# V1-MOUSE-REVIEW.net
KiCad netlist of a schematic drawn in EAGLE
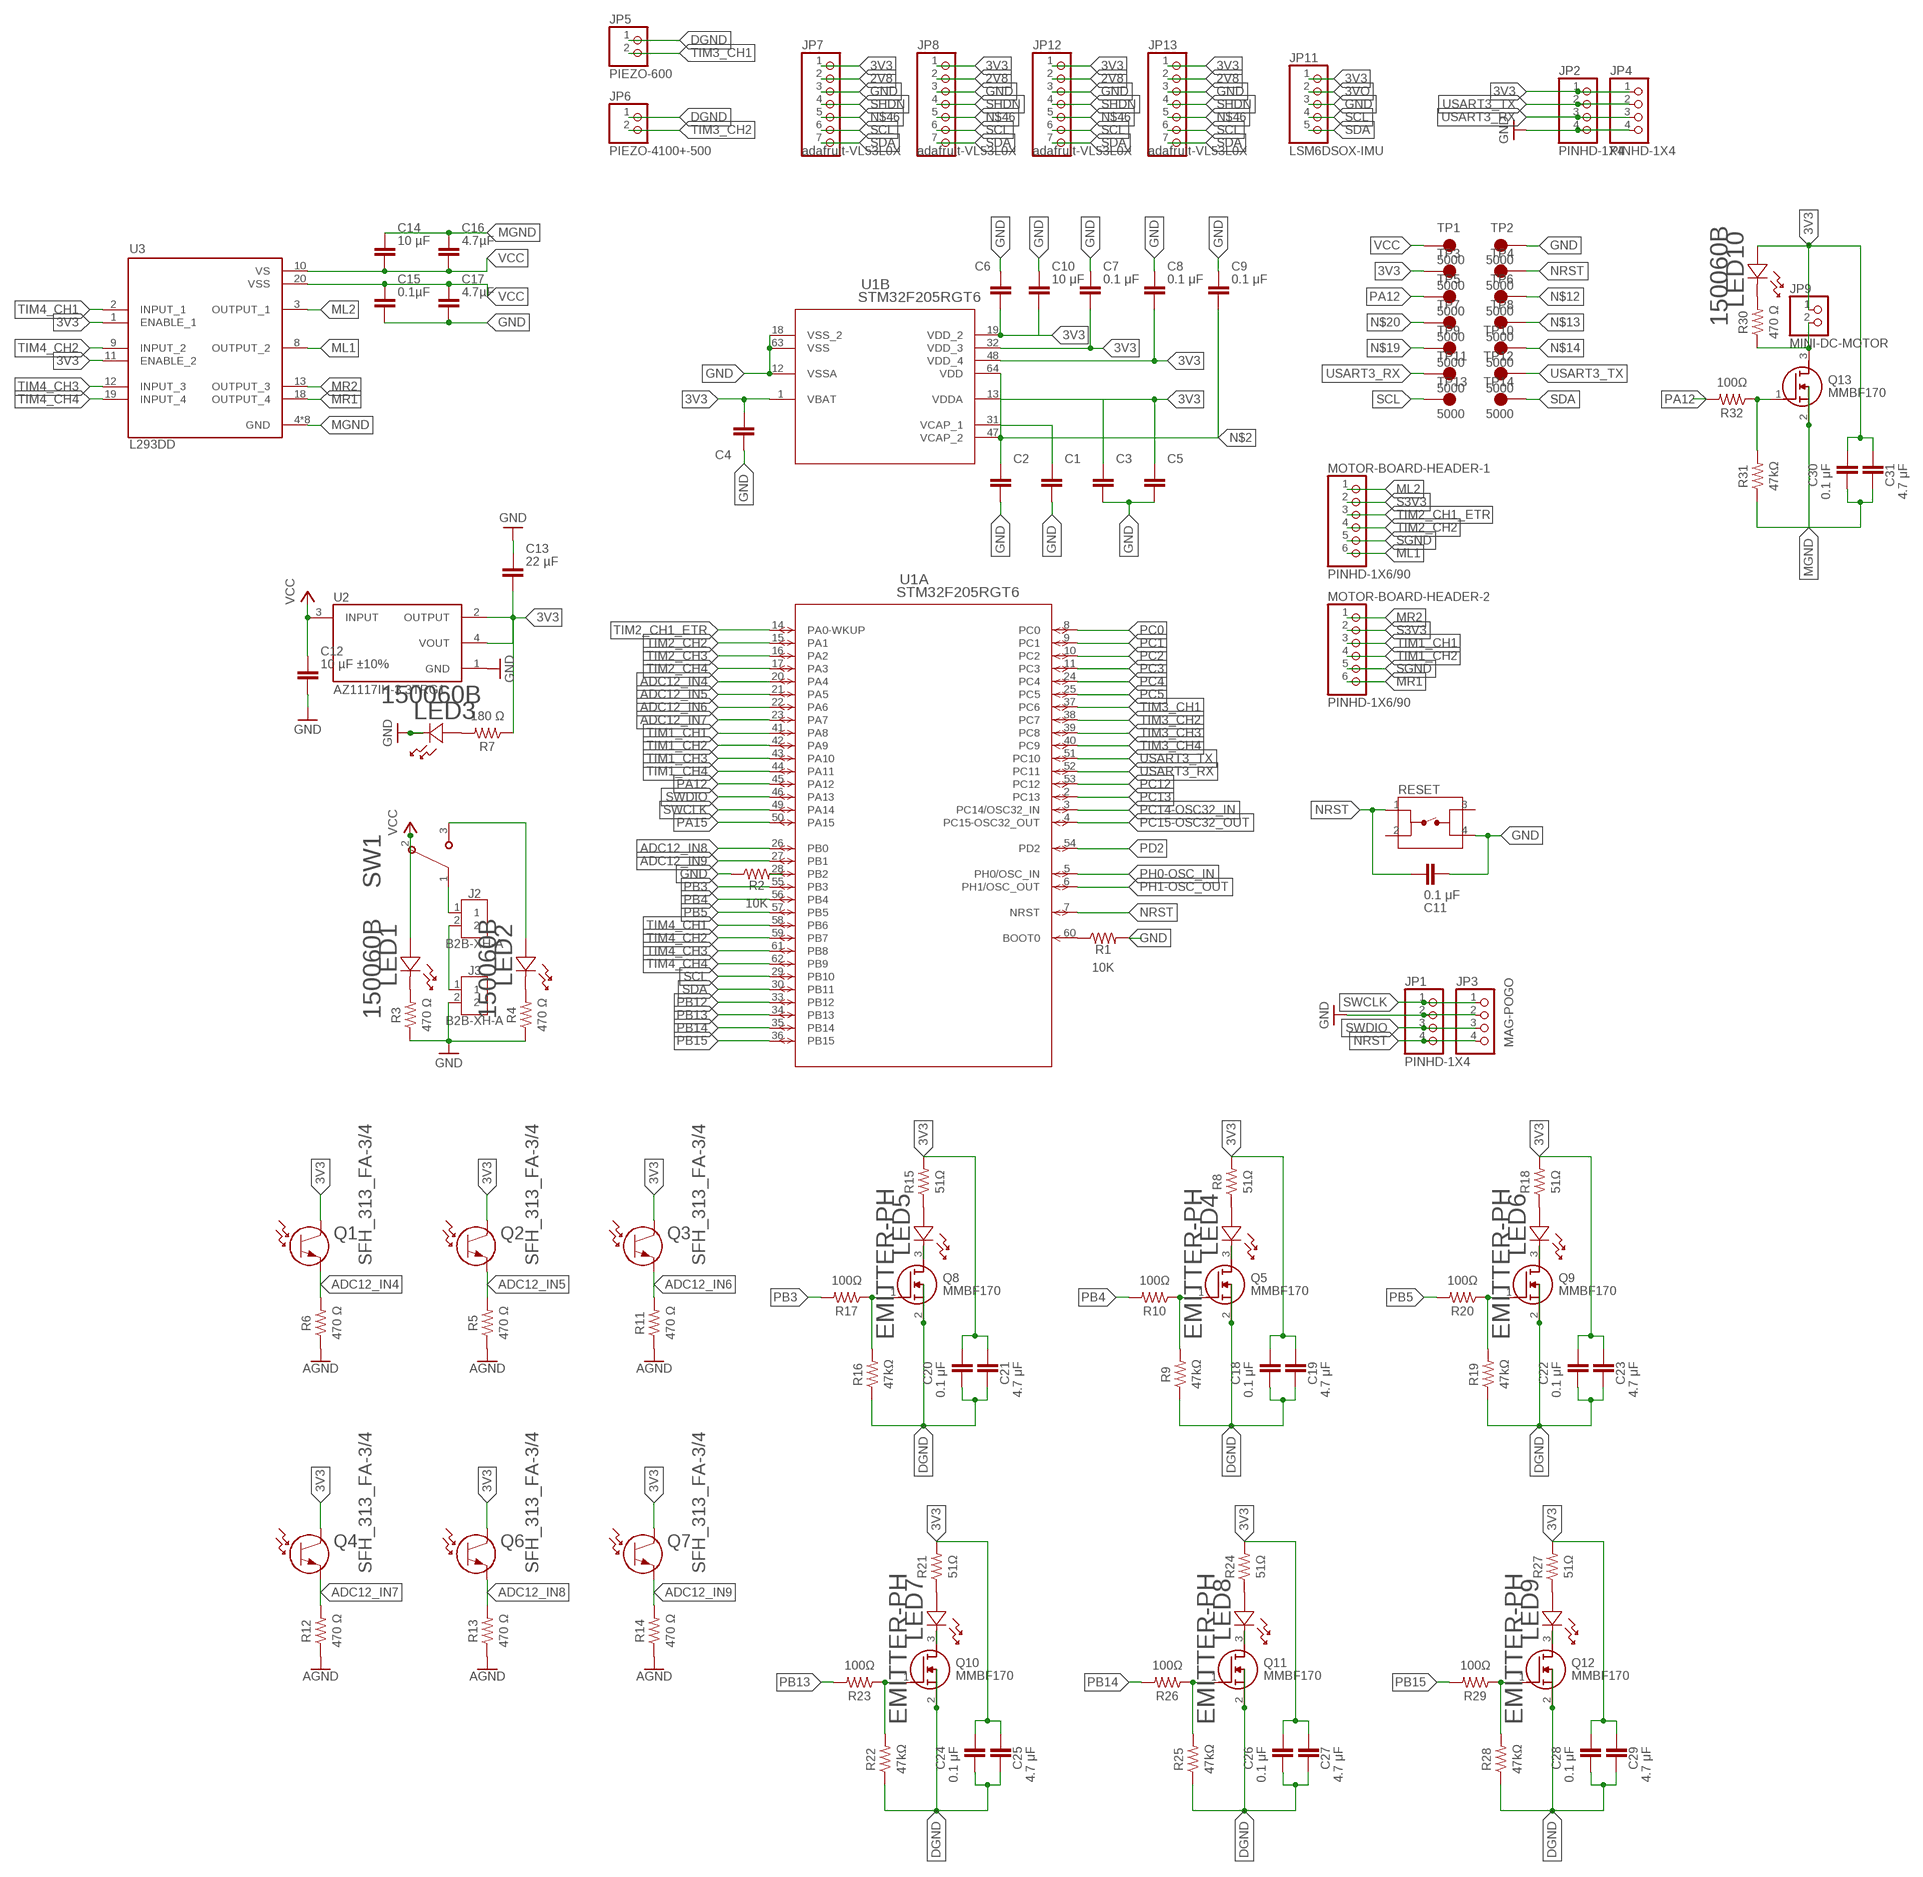
[diagram p0: schematic, sheet 1]

(export (version "E")
  (design (tool "Eeschema 10.0.6"))
  (components
    (comp (ref "C1")
      (value "2.2 μF")
      (footprint "eagle-import:CAPC1608X85")
      (libsource (lib "eagle-import") (part "CCHIP-0603(1608-METRIC)_"))
    )
    (comp (ref "C2")
      (value "2.2 μF")
      (footprint "eagle-import:CAPC1608X85")
      (libsource (lib "eagle-import") (part "CCHIP-0603(1608-METRIC)_"))
    )
    (comp (ref "C3")
      (value "0.1 μF")
      (footprint "eagle-import:CAPC1608X85")
      (libsource (lib "eagle-import") (part "CCHIP-0603(1608-METRIC)_"))
    )
    (comp (ref "C4")
      (value "0.1 μF")
      (footprint "eagle-import:CAPC1608X85")
      (libsource (lib "eagle-import") (part "CCHIP-0603(1608-METRIC)_"))
    )
    (comp (ref "C5")
      (value "1 μF")
      (footprint "eagle-import:CAPC1608X85")
      (libsource (lib "eagle-import") (part "CCHIP-0603(1608-METRIC)_"))
    )
    (comp (ref "C6")
      (value "0.1 μF")
      (footprint "eagle-import:CAPC1608X85")
      (libsource (lib "eagle-import") (part "CCHIP-0603(1608-METRIC)_"))
    )
    (comp (ref "C7")
      (value "0.1 μF")
      (footprint "eagle-import:CAPC1608X85")
      (libsource (lib "eagle-import") (part "Capacitor2_CCHIP-0603(1608-METRIC)_"))
    )
    (comp (ref "C8")
      (value "0.1 μF")
      (footprint "eagle-import:CAPC1608X85")
      (libsource (lib "eagle-import") (part "Capacitor2_CCHIP-0603(1608-METRIC)_"))
    )
    (comp (ref "C9")
      (value "0.1 μF")
      (footprint "eagle-import:CAPC1608X85")
      (libsource (lib "eagle-import") (part "Capacitor2_CCHIP-0603(1608-METRIC)_"))
    )
    (comp (ref "C10")
      (value "10 μF")
      (footprint "eagle-import:CAPC1608X85")
      (libsource (lib "eagle-import") (part "Capacitor2_CCHIP-0603(1608-METRIC)_"))
    )
    (comp (ref "C11")
      (value "0.1 μF")
      (footprint "eagle-import:CAPC1608X85")
      (libsource (lib "eagle-import") (part "Capacitor2_CCHIP-0603(1608-METRIC)_"))
    )
    (comp (ref "C12")
      (value "10 µF ±10%")
      (footprint "eagle-import:CAPC1608X85")
      (libsource (lib "eagle-import") (part "CCHIP-0603(1608-METRIC)_"))
    )
    (comp (ref "C13")
      (value "22 µF")
      (footprint "eagle-import:CAPC1608X85")
      (libsource (lib "eagle-import") (part "CCHIP-0603(1608-METRIC)_"))
    )
    (comp (ref "C14")
      (value "10 µF")
      (footprint "eagle-import:CAPC1608X85")
      (libsource (lib "eagle-import") (part "CCHIP-0603(1608-METRIC)_"))
    )
    (comp (ref "C15")
      (value "0.1µF")
      (footprint "eagle-import:CAPC1608X85")
      (libsource (lib "eagle-import") (part "CCHIP-0603(1608-METRIC)_"))
    )
    (comp (ref "C16")
      (value "4.7µF")
      (footprint "eagle-import:CAPC1608X85")
      (libsource (lib "eagle-import") (part "CCHIP-0603(1608-METRIC)_"))
    )
    (comp (ref "C17")
      (value "4.7µF")
      (footprint "eagle-import:CAPC1608X85")
      (libsource (lib "eagle-import") (part "CCHIP-0603(1608-METRIC)_"))
    )
    (comp (ref "C18")
      (value "0.1 μF")
      (footprint "eagle-import:CAPC1608X85")
      (libsource (lib "eagle-import") (part "Capacitor2_CCHIP-0603(1608-METRIC)_"))
    )
    (comp (ref "C19")
      (value "4.7 μF")
      (footprint "eagle-import:CAPC1608X85")
      (libsource (lib "eagle-import") (part "Capacitor2_CCHIP-0603(1608-METRIC)_"))
    )
    (comp (ref "C20")
      (value "0.1 μF")
      (footprint "eagle-import:CAPC1608X85")
      (libsource (lib "eagle-import") (part "Capacitor2_CCHIP-0603(1608-METRIC)_"))
    )
    (comp (ref "C21")
      (value "4.7 μF")
      (footprint "eagle-import:CAPC1608X85")
      (libsource (lib "eagle-import") (part "Capacitor2_CCHIP-0603(1608-METRIC)_"))
    )
    (comp (ref "C22")
      (value "0.1 μF")
      (footprint "eagle-import:CAPC1608X85")
      (libsource (lib "eagle-import") (part "Capacitor2_CCHIP-0603(1608-METRIC)_"))
    )
    (comp (ref "C23")
      (value "4.7 μF")
      (footprint "eagle-import:CAPC1608X85")
      (libsource (lib "eagle-import") (part "Capacitor2_CCHIP-0603(1608-METRIC)_"))
    )
    (comp (ref "C24")
      (value "0.1 μF")
      (footprint "eagle-import:CAPC1608X85")
      (libsource (lib "eagle-import") (part "Capacitor2_CCHIP-0603(1608-METRIC)_"))
    )
    (comp (ref "C25")
      (value "4.7 μF")
      (footprint "eagle-import:CAPC1608X85")
      (libsource (lib "eagle-import") (part "Capacitor2_CCHIP-0603(1608-METRIC)_"))
    )
    (comp (ref "C26")
      (value "0.1 μF")
      (footprint "eagle-import:CAPC1608X85")
      (libsource (lib "eagle-import") (part "Capacitor2_CCHIP-0603(1608-METRIC)_"))
    )
    (comp (ref "C27")
      (value "4.7 μF")
      (footprint "eagle-import:CAPC1608X85")
      (libsource (lib "eagle-import") (part "Capacitor2_CCHIP-0603(1608-METRIC)_"))
    )
    (comp (ref "C28")
      (value "0.1 μF")
      (footprint "eagle-import:CAPC1608X85")
      (libsource (lib "eagle-import") (part "Capacitor2_CCHIP-0603(1608-METRIC)_"))
    )
    (comp (ref "C29")
      (value "4.7 μF")
      (footprint "eagle-import:CAPC1608X85")
      (libsource (lib "eagle-import") (part "Capacitor2_CCHIP-0603(1608-METRIC)_"))
    )
    (comp (ref "C30")
      (value "0.1 μF")
      (footprint "eagle-import:CAPC1608X85")
      (libsource (lib "eagle-import") (part "Capacitor2_CCHIP-0603(1608-METRIC)_"))
    )
    (comp (ref "C31")
      (value "4.7 μF")
      (footprint "eagle-import:CAPC1608X85")
      (libsource (lib "eagle-import") (part "Capacitor2_CCHIP-0603(1608-METRIC)_"))
    )
    (comp (ref "J2")
      (value "B2B-XH-A")
      (footprint "eagle-import:B2B-XH-A")
      (fields
        (field (name "MANUFACTURER") "JST Sales America Inc. ")
        (field (name "MPN") "B2B-XH-A(LF)(SN) ")
      )
      (libsource (lib "eagle-import") (part "B2B-XH-A"))
    )
    (comp (ref "J3")
      (value "B2B-XH-A")
      (footprint "eagle-import:B2B-XH-A")
      (fields
        (field (name "MANUFACTURER") "JST Sales America Inc. ")
        (field (name "MPN") "B2B-XH-A(LF)(SN) ")
      )
      (libsource (lib "eagle-import") (part "B2B-XH-A"))
    )
    (comp (ref "JP1")
      (value "PINHD-1X4")
      (footprint "eagle-import:1X04")
      (fields (field (name "MANUFACTURER") "Generic"))
      (libsource (lib "eagle-import") (part "PINHD-1X4"))
    )
    (comp (ref "JP2")
      (value "PINHD-1X4")
      (footprint "eagle-import:1X04")
      (fields (field (name "MANUFACTURER") "Generic"))
      (libsource (lib "eagle-import") (part "PINHD-1X4"))
    )
    (comp (ref "JP3")
      (value "MAG-POGO")
      (footprint "eagle-import:1X04")
      (fields (field (name "MANUFACTURER") "Generic"))
      (libsource (lib "eagle-import") (part "PINHD-1X4"))
    )
    (comp (ref "JP4")
      (value "PINHD-1X4")
      (footprint "eagle-import:1X04")
      (fields (field (name "MANUFACTURER") "Generic"))
      (libsource (lib "eagle-import") (part "PINHD-1X4"))
    )
    (comp (ref "JP5")
      (value "PIEZO-600")
      (footprint "eagle-import:1X02_90")
      (fields (field (name "MANUFACTURER") "Generic"))
      (libsource (lib "eagle-import") (part "PINHD-1X2/90"))
    )
    (comp (ref "JP6")
      (value "PIEZO-4100+-500")
      (footprint "eagle-import:1X02_90")
      (fields (field (name "MANUFACTURER") "Generic"))
      (libsource (lib "eagle-import") (part "PINHD-1X2/90"))
    )
    (comp (ref "JP7")
      (value "adafruit-VL53L0X")
      (footprint "eagle-import:1X07_90")
      (fields (field (name "MANUFACTURER") "Generic"))
      (libsource (lib "eagle-import") (part "PINHD-1X7/90"))
    )
    (comp (ref "JP8")
      (value "adafruit-VL53L0X")
      (footprint "eagle-import:1X07_90")
      (fields (field (name "MANUFACTURER") "Generic"))
      (libsource (lib "eagle-import") (part "PINHD-1X7/90"))
    )
    (comp (ref "JP9")
      (value "MINI-DC-MOTOR")
      (footprint "eagle-import:1X02")
      (fields (field (name "MANUFACTURER") "Generic"))
      (libsource (lib "eagle-import") (part "PINHD-1X2"))
    )
    (comp (ref "JP11")
      (value "LSM6DSOX-IMU")
      (footprint "eagle-import:1_05X2MM")
      (fields (field (name "MANUFACTURER") "Generic"))
      (libsource (lib "eagle-import") (part "PINHD-1X55X2MM"))
    )
    (comp (ref "JP12")
      (value "adafruit-VL53L0X")
      (footprint "eagle-import:1X07_90")
      (fields (field (name "MANUFACTURER") "Generic"))
      (libsource (lib "eagle-import") (part "PINHD-1X7/90"))
    )
    (comp (ref "JP13")
      (value "adafruit-VL53L0X")
      (footprint "eagle-import:1X07_90")
      (fields (field (name "MANUFACTURER") "Generic"))
      (libsource (lib "eagle-import") (part "PINHD-1X7/90"))
    )
    (comp (ref "LED1")
      (value "150060B")
      (footprint "eagle-import:LED_150060B_WRE-L")
      (fields
        (field (name "MANUFACTURER_PART_NUMBER") "150060VS55040")
        (field (name "COPYRIGHT") "Copyright (C) 2024 Ultra Librarian. All rights reserved.")
      )
      (libsource (lib "eagle-import") (part "150060VS55040LED_150060B_WRE-L"))
    )
    (comp (ref "LED2")
      (value "150060B")
      (footprint "eagle-import:LED_150060B_WRE-L")
      (fields
        (field (name "MANUFACTURER_PART_NUMBER") "150060VS55040")
        (field (name "COPYRIGHT") "Copyright (C) 2024 Ultra Librarian. All rights reserved.")
      )
      (libsource (lib "eagle-import") (part "150060VS55040LED_150060B_WRE-L"))
    )
    (comp (ref "LED3")
      (value "150060B")
      (footprint "eagle-import:LED_150060B_WRE-L")
      (fields
        (field (name "MANUFACTURER_PART_NUMBER") "150060VS55040")
        (field (name "COPYRIGHT") "Copyright (C) 2024 Ultra Librarian. All rights reserved.")
      )
      (libsource (lib "eagle-import") (part "150060VS55040LED_150060B_WRE-L"))
    )
    (comp (ref "LED4")
      (value "EMITTER-PH")
      (footprint "eagle-import:LED_B1911PG--20D000514U1930_01")
      (fields
        (field (name "MANUFACTURER_PART_NUMBER") "B1911PG--20D000514U1930")
        (field (name "COPYRIGHT") "Copyright (C) 2024 Ultra Librarian. All rights reserved.")
      )
      (libsource (lib "eagle-import") (part "B1911PG--20D000514U1930LED_B1911PG--20D000514U1930_01"))
    )
    (comp (ref "LED5")
      (value "EMITTER-PH")
      (footprint "eagle-import:LED_B1911PG--20D000514U1930_01")
      (fields
        (field (name "MANUFACTURER_PART_NUMBER") "B1911PG--20D000514U1930")
        (field (name "COPYRIGHT") "Copyright (C) 2024 Ultra Librarian. All rights reserved.")
      )
      (libsource (lib "eagle-import") (part "B1911PG--20D000514U1930LED_B1911PG--20D000514U1930_01"))
    )
    (comp (ref "LED6")
      (value "EMITTER-PH")
      (footprint "eagle-import:LED_B1911PG--20D000514U1930_01")
      (fields
        (field (name "MANUFACTURER_PART_NUMBER") "B1911PG--20D000514U1930")
        (field (name "COPYRIGHT") "Copyright (C) 2024 Ultra Librarian. All rights reserved.")
      )
      (libsource (lib "eagle-import") (part "B1911PG--20D000514U1930LED_B1911PG--20D000514U1930_01"))
    )
    (comp (ref "LED7")
      (value "EMITTER-PH")
      (footprint "eagle-import:LED_B1911PG--20D000514U1930_01")
      (fields
        (field (name "MANUFACTURER_PART_NUMBER") "B1911PG--20D000514U1930")
        (field (name "COPYRIGHT") "Copyright (C) 2024 Ultra Librarian. All rights reserved.")
      )
      (libsource (lib "eagle-import") (part "B1911PG--20D000514U1930LED_B1911PG--20D000514U1930_01"))
    )
    (comp (ref "LED8")
      (value "EMITTER-PH")
      (footprint "eagle-import:LED_B1911PG--20D000514U1930_01")
      (fields
        (field (name "MANUFACTURER_PART_NUMBER") "B1911PG--20D000514U1930")
        (field (name "COPYRIGHT") "Copyright (C) 2024 Ultra Librarian. All rights reserved.")
      )
      (libsource (lib "eagle-import") (part "B1911PG--20D000514U1930LED_B1911PG--20D000514U1930_01"))
    )
    (comp (ref "LED9")
      (value "EMITTER-PH")
      (footprint "eagle-import:LED_B1911PG--20D000514U1930_01")
      (fields
        (field (name "MANUFACTURER_PART_NUMBER") "B1911PG--20D000514U1930")
        (field (name "COPYRIGHT") "Copyright (C) 2024 Ultra Librarian. All rights reserved.")
      )
      (libsource (lib "eagle-import") (part "B1911PG--20D000514U1930LED_B1911PG--20D000514U1930_01"))
    )
    (comp (ref "LED10")
      (value "150060B")
      (footprint "eagle-import:LED_150060B_WRE-L")
      (fields
        (field (name "MANUFACTURER_PART_NUMBER") "150060VS55040")
        (field (name "COPYRIGHT") "Copyright (C) 2024 Ultra Librarian. All rights reserved.")
      )
      (libsource (lib "eagle-import") (part "150060VS55040LED_150060B_WRE-L"))
    )
    (comp (ref "MOTOR-BOARD-HEADER-1")
      (value "PINHD-1X6/90")
      (footprint "eagle-import:1X06_90")
      (fields (field (name "MANUFACTURER") "Generic"))
      (libsource (lib "eagle-import") (part "PINHD-1X6/90"))
    )
    (comp (ref "MOTOR-BOARD-HEADER-2")
      (value "PINHD-1X6/90")
      (footprint "eagle-import:1X06_90")
      (fields (field (name "MANUFACTURER") "Generic"))
      (libsource (lib "eagle-import") (part "PINHD-1X6/90"))
    )
    (comp (ref "Q1")
      (value "SFH_313_FA-3/4")
      (footprint "eagle-import:SFH_313_FA-3_4_OSR")
      (fields
        (field (name "MANUFACTURER_PART_NUMBER") "SFH 313 FA-3/4")
        (field (name "COPYRIGHT") "Copyright (C) 2024 Ultra Librarian. All rights reserved.")
      )
      (libsource (lib "eagle-import") (part "SFH_313_FA-3/4SFH_313_FA-3/4_OSR"))
    )
    (comp (ref "Q2")
      (value "SFH_313_FA-3/4")
      (footprint "eagle-import:SFH_313_FA-3_4_OSR")
      (fields
        (field (name "MANUFACTURER_PART_NUMBER") "SFH 313 FA-3/4")
        (field (name "COPYRIGHT") "Copyright (C) 2024 Ultra Librarian. All rights reserved.")
      )
      (libsource (lib "eagle-import") (part "SFH_313_FA-3/4SFH_313_FA-3/4_OSR"))
    )
    (comp (ref "Q3")
      (value "SFH_313_FA-3/4")
      (footprint "eagle-import:SFH_313_FA-3_4_OSR")
      (fields
        (field (name "MANUFACTURER_PART_NUMBER") "SFH 313 FA-3/4")
        (field (name "COPYRIGHT") "Copyright (C) 2024 Ultra Librarian. All rights reserved.")
      )
      (libsource (lib "eagle-import") (part "SFH_313_FA-3/4SFH_313_FA-3/4_OSR"))
    )
    (comp (ref "Q4")
      (value "SFH_313_FA-3/4")
      (footprint "eagle-import:SFH_313_FA-3_4_OSR")
      (fields
        (field (name "MANUFACTURER_PART_NUMBER") "SFH 313 FA-3/4")
        (field (name "COPYRIGHT") "Copyright (C) 2024 Ultra Librarian. All rights reserved.")
      )
      (libsource (lib "eagle-import") (part "SFH_313_FA-3/4SFH_313_FA-3/4_OSR"))
    )
    (comp (ref "Q5")
      (value "MMBF170")
      (footprint "eagle-import:SOT96P237X111-3N")
      (fields (field (name "MOUSER_PART_NUMBER") "512-MMBF170"))
      (libsource (lib "eagle-import") (part "MMBF170"))
    )
    (comp (ref "Q6")
      (value "SFH_313_FA-3/4")
      (footprint "eagle-import:SFH_313_FA-3_4_OSR")
      (fields
        (field (name "MANUFACTURER_PART_NUMBER") "SFH 313 FA-3/4")
        (field (name "COPYRIGHT") "Copyright (C) 2024 Ultra Librarian. All rights reserved.")
      )
      (libsource (lib "eagle-import") (part "SFH_313_FA-3/4SFH_313_FA-3/4_OSR"))
    )
    (comp (ref "Q7")
      (value "SFH_313_FA-3/4")
      (footprint "eagle-import:SFH_313_FA-3_4_OSR")
      (fields
        (field (name "MANUFACTURER_PART_NUMBER") "SFH 313 FA-3/4")
        (field (name "COPYRIGHT") "Copyright (C) 2024 Ultra Librarian. All rights reserved.")
      )
      (libsource (lib "eagle-import") (part "SFH_313_FA-3/4SFH_313_FA-3/4_OSR"))
    )
    (comp (ref "Q8")
      (value "MMBF170")
      (footprint "eagle-import:SOT96P237X111-3N")
      (fields (field (name "MOUSER_PART_NUMBER") "512-MMBF170"))
      (libsource (lib "eagle-import") (part "MMBF170"))
    )
    (comp (ref "Q9")
      (value "MMBF170")
      (footprint "eagle-import:SOT96P237X111-3N")
      (fields (field (name "MOUSER_PART_NUMBER") "512-MMBF170"))
      (libsource (lib "eagle-import") (part "MMBF170"))
    )
    (comp (ref "Q10")
      (value "MMBF170")
      (footprint "eagle-import:SOT96P237X111-3N")
      (fields (field (name "MOUSER_PART_NUMBER") "512-MMBF170"))
      (libsource (lib "eagle-import") (part "MMBF170"))
    )
    (comp (ref "Q11")
      (value "MMBF170")
      (footprint "eagle-import:SOT96P237X111-3N")
      (fields (field (name "MOUSER_PART_NUMBER") "512-MMBF170"))
      (libsource (lib "eagle-import") (part "MMBF170"))
    )
    (comp (ref "Q12")
      (value "MMBF170")
      (footprint "eagle-import:SOT96P237X111-3N")
      (fields (field (name "MOUSER_PART_NUMBER") "512-MMBF170"))
      (libsource (lib "eagle-import") (part "MMBF170"))
    )
    (comp (ref "Q13")
      (value "MMBF170")
      (footprint "eagle-import:SOT96P237X111-3N")
      (fields (field (name "MOUSER_PART_NUMBER") "512-MMBF170"))
      (libsource (lib "eagle-import") (part "MMBF170"))
    )
    (comp (ref "R1")
      (value "10K")
      (footprint "eagle-import:RESC1608X60")
      (libsource (lib "eagle-import") (part "Resistor2_R-USCHIP-0603(1608-METRIC)_"))
    )
    (comp (ref "R2")
      (value "10K")
      (footprint "eagle-import:RESC1608X60")
      (libsource (lib "eagle-import") (part "Resistor2_R-USCHIP-0603(1608-METRIC)_"))
    )
    (comp (ref "R3")
      (value "470 Ω")
      (footprint "eagle-import:RESC1608X60")
      (libsource (lib "eagle-import") (part "R-USCHIP-0603(1608-METRIC)_"))
    )
    (comp (ref "R4")
      (value "470 Ω")
      (footprint "eagle-import:RESC1608X60")
      (libsource (lib "eagle-import") (part "R-USCHIP-0603(1608-METRIC)_"))
    )
    (comp (ref "R5")
      (value "470 Ω")
      (footprint "eagle-import:RESC1608X60")
      (libsource (lib "eagle-import") (part "R-USCHIP-0603(1608-METRIC)_"))
    )
    (comp (ref "R6")
      (value "470 Ω")
      (footprint "eagle-import:RESC1608X60")
      (libsource (lib "eagle-import") (part "R-USCHIP-0603(1608-METRIC)_"))
    )
    (comp (ref "R7")
      (value "180 Ω")
      (footprint "eagle-import:RESC1608X60")
      (libsource (lib "eagle-import") (part "R-USCHIP-0603(1608-METRIC)_"))
    )
    (comp (ref "R8")
      (value "51Ω")
      (footprint "eagle-import:RESC1608X60")
      (libsource (lib "eagle-import") (part "R-USCHIP-0603(1608-METRIC)_"))
    )
    (comp (ref "R9")
      (value "47kΩ")
      (footprint "eagle-import:RESC1608X60")
      (libsource (lib "eagle-import") (part "R-USCHIP-0603(1608-METRIC)_"))
    )
    (comp (ref "R10")
      (value "100Ω")
      (footprint "eagle-import:RESC1608X60")
      (libsource (lib "eagle-import") (part "R-USCHIP-0603(1608-METRIC)_"))
    )
    (comp (ref "R11")
      (value "470 Ω")
      (footprint "eagle-import:RESC1608X60")
      (libsource (lib "eagle-import") (part "R-USCHIP-0603(1608-METRIC)_"))
    )
    (comp (ref "R12")
      (value "470 Ω")
      (footprint "eagle-import:RESC1608X60")
      (libsource (lib "eagle-import") (part "R-USCHIP-0603(1608-METRIC)_"))
    )
    (comp (ref "R13")
      (value "470 Ω")
      (footprint "eagle-import:RESC1608X60")
      (libsource (lib "eagle-import") (part "R-USCHIP-0603(1608-METRIC)_"))
    )
    (comp (ref "R14")
      (value "470 Ω")
      (footprint "eagle-import:RESC1608X60")
      (libsource (lib "eagle-import") (part "R-USCHIP-0603(1608-METRIC)_"))
    )
    (comp (ref "R15")
      (value "51Ω")
      (footprint "eagle-import:RESC1608X60")
      (libsource (lib "eagle-import") (part "R-USCHIP-0603(1608-METRIC)_"))
    )
    (comp (ref "R16")
      (value "47kΩ")
      (footprint "eagle-import:RESC1608X60")
      (libsource (lib "eagle-import") (part "R-USCHIP-0603(1608-METRIC)_"))
    )
    (comp (ref "R17")
      (value "100Ω")
      (footprint "eagle-import:RESC1608X60")
      (libsource (lib "eagle-import") (part "R-USCHIP-0603(1608-METRIC)_"))
    )
    (comp (ref "R18")
      (value "51Ω")
      (footprint "eagle-import:RESC1608X60")
      (libsource (lib "eagle-import") (part "R-USCHIP-0603(1608-METRIC)_"))
    )
    (comp (ref "R19")
      (value "47kΩ")
      (footprint "eagle-import:RESC1608X60")
      (libsource (lib "eagle-import") (part "R-USCHIP-0603(1608-METRIC)_"))
    )
    (comp (ref "R20")
      (value "100Ω")
      (footprint "eagle-import:RESC1608X60")
      (libsource (lib "eagle-import") (part "R-USCHIP-0603(1608-METRIC)_"))
    )
    (comp (ref "R21")
      (value "51Ω")
      (footprint "eagle-import:RESC1608X60")
      (libsource (lib "eagle-import") (part "R-USCHIP-0603(1608-METRIC)_"))
    )
    (comp (ref "R22")
      (value "47kΩ")
      (footprint "eagle-import:RESC1608X60")
      (libsource (lib "eagle-import") (part "R-USCHIP-0603(1608-METRIC)_"))
    )
    (comp (ref "R23")
      (value "100Ω")
      (footprint "eagle-import:RESC1608X60")
      (libsource (lib "eagle-import") (part "R-USCHIP-0603(1608-METRIC)_"))
    )
    (comp (ref "R24")
      (value "51Ω")
      (footprint "eagle-import:RESC1608X60")
      (libsource (lib "eagle-import") (part "R-USCHIP-0603(1608-METRIC)_"))
    )
    (comp (ref "R25")
      (value "47kΩ")
      (footprint "eagle-import:RESC1608X60")
      (libsource (lib "eagle-import") (part "R-USCHIP-0603(1608-METRIC)_"))
    )
    (comp (ref "R26")
      (value "100Ω")
      (footprint "eagle-import:RESC1608X60")
      (libsource (lib "eagle-import") (part "R-USCHIP-0603(1608-METRIC)_"))
    )
    (comp (ref "R27")
      (value "51Ω")
      (footprint "eagle-import:RESC1608X60")
      (libsource (lib "eagle-import") (part "R-USCHIP-0603(1608-METRIC)_"))
    )
    (comp (ref "R28")
      (value "47kΩ")
      (footprint "eagle-import:RESC1608X60")
      (libsource (lib "eagle-import") (part "R-USCHIP-0603(1608-METRIC)_"))
    )
    (comp (ref "R29")
      (value "100Ω")
      (footprint "eagle-import:RESC1608X60")
      (libsource (lib "eagle-import") (part "R-USCHIP-0603(1608-METRIC)_"))
    )
    (comp (ref "R30")
      (value "470 Ω")
      (footprint "eagle-import:RESC1608X60")
      (libsource (lib "eagle-import") (part "R-USCHIP-0603(1608-METRIC)_"))
    )
    (comp (ref "R31")
      (value "47kΩ")
      (footprint "eagle-import:RESC1608X60")
      (libsource (lib "eagle-import") (part "R-USCHIP-0603(1608-METRIC)_"))
    )
    (comp (ref "R32")
      (value "100Ω")
      (footprint "eagle-import:RESC1608X60")
      (libsource (lib "eagle-import") (part "R-USCHIP-0603(1608-METRIC)_"))
    )
    (comp (ref "RESET")
      (value "FSM4JSMA")
      (footprint "eagle-import:TE_FSM4JSMA")
      (fields
        (field (name "COMMENT") "4-1437565-1")
        (field (name "DIGI-KEY_PART_NUMBER") "450-1759-2-ND")
        (field (name "MF") "TE Connectivity")
      )
      (libsource (lib "eagle-import") (part "FSM4JSMA"))
    )
    (comp (ref "SW1")
      (value "EG1218SW_1218_EWI")
      (footprint "eagle-import:SW_1218_EWI")
      (fields
        (field (name "MANUFACTURER_PART_NUMBER") "EG1218")
        (field (name "COPYRIGHT") "Copyright (C) 2024 Ultra Librarian. All rights reserved.")
      )
      (libsource (lib "eagle-import") (part "EG1218SW_1218_EWI"))
    )
    (comp (ref "TP1")
      (value "5000")
      (footprint "eagle-import:KEYSTONE_5000")
      (fields (field (name "MF") "Keystone Electronics"))
      (libsource (lib "eagle-import") (part "5000"))
    )
    (comp (ref "TP2")
      (value "5000")
      (footprint "eagle-import:KEYSTONE_5000")
      (fields (field (name "MF") "Keystone Electronics"))
      (libsource (lib "eagle-import") (part "5000"))
    )
    (comp (ref "TP3")
      (value "5000")
      (footprint "eagle-import:KEYSTONE_5000")
      (fields (field (name "MF") "Keystone Electronics"))
      (libsource (lib "eagle-import") (part "5000"))
    )
    (comp (ref "TP4")
      (value "5000")
      (footprint "eagle-import:KEYSTONE_5000")
      (fields (field (name "MF") "Keystone Electronics"))
      (libsource (lib "eagle-import") (part "5000"))
    )
    (comp (ref "TP5")
      (value "5000")
      (footprint "eagle-import:KEYSTONE_5000")
      (fields (field (name "MF") "Keystone Electronics"))
      (libsource (lib "eagle-import") (part "5000"))
    )
    (comp (ref "TP6")
      (value "5000")
      (footprint "eagle-import:KEYSTONE_5000")
      (fields (field (name "MF") "Keystone Electronics"))
      (libsource (lib "eagle-import") (part "5000"))
    )
    (comp (ref "TP7")
      (value "5000")
      (footprint "eagle-import:KEYSTONE_5000")
      (fields (field (name "MF") "Keystone Electronics"))
      (libsource (lib "eagle-import") (part "5000"))
    )
    (comp (ref "TP8")
      (value "5000")
      (footprint "eagle-import:KEYSTONE_5000")
      (fields (field (name "MF") "Keystone Electronics"))
      (libsource (lib "eagle-import") (part "5000"))
    )
    (comp (ref "TP9")
      (value "5000")
      (footprint "eagle-import:KEYSTONE_5000")
      (fields (field (name "MF") "Keystone Electronics"))
      (libsource (lib "eagle-import") (part "5000"))
    )
    (comp (ref "TP10")
      (value "5000")
      (footprint "eagle-import:KEYSTONE_5000")
      (fields (field (name "MF") "Keystone Electronics"))
      (libsource (lib "eagle-import") (part "5000"))
    )
    (comp (ref "TP11")
      (value "5000")
      (footprint "eagle-import:KEYSTONE_5000")
      (fields (field (name "MF") "Keystone Electronics"))
      (libsource (lib "eagle-import") (part "5000"))
    )
    (comp (ref "TP12")
      (value "5000")
      (footprint "eagle-import:KEYSTONE_5000")
      (fields (field (name "MF") "Keystone Electronics"))
      (libsource (lib "eagle-import") (part "5000"))
    )
    (comp (ref "TP13")
      (value "5000")
      (footprint "eagle-import:KEYSTONE_5000")
      (fields (field (name "MF") "Keystone Electronics"))
      (libsource (lib "eagle-import") (part "5000"))
    )
    (comp (ref "TP14")
      (value "5000")
      (footprint "eagle-import:KEYSTONE_5000")
      (fields (field (name "MF") "Keystone Electronics"))
      (libsource (lib "eagle-import") (part "5000"))
    )
    (comp (ref "U1")
      (value "STM32F205RGT6")
      (footprint "eagle-import:LQFP64-10X10MM")
      (fields (field (name "COPYRIGHT") "Copyright (C) 2021 Ultra Librarian. All rights reserved."))
      (libsource (lib "eagle-import") (part "STM32F205RGT6"))
    )
    (comp (ref "U2")
      (value "AZ1117IH-3.3TRG1")
      (footprint "eagle-import:SOT230P700X185-4N")
      (fields (field (name "MF") "Diodes Inc."))
      (libsource (lib "eagle-import") (part "AZ1117IH-3.3TRG1"))
    )
    (comp (ref "U3")
      (value "L293DD")
      (footprint "eagle-import:SOIC127P1032X265-20N")
      (fields (field (name "MANUFACTURER") "STMicroelectronics"))
      (libsource (lib "eagle-import") (part "L293DD"))
    )
  )
  (nets
    (net (code "1") (name "2V8") (class "Default")
      (node (ref "JP12") (pin "2") (pinfunction "2_2") (pintype "passive"))
      (node (ref "JP13") (pin "2") (pinfunction "2_2") (pintype "passive"))
      (node (ref "JP7") (pin "2") (pinfunction "2_2") (pintype "passive"))
      (node (ref "JP8") (pin "2") (pinfunction "2_2") (pintype "passive"))
    )
    (net (code "2") (name "3V3") (class "Default")
      (node (ref "C10") (pin "2") (pinfunction "2_2") (pintype "passive"))
      (node (ref "C13") (pin "2") (pinfunction "2_2") (pintype "passive"))
      (node (ref "C18") (pin "2") (pinfunction "2_2") (pintype "passive"))
      (node (ref "C19") (pin "2") (pinfunction "2_2") (pintype "passive"))
      (node (ref "C20") (pin "2") (pinfunction "2_2") (pintype "passive"))
      (node (ref "C21") (pin "2") (pinfunction "2_2") (pintype "passive"))
      (node (ref "C22") (pin "2") (pinfunction "2_2") (pintype "passive"))
      (node (ref "C23") (pin "2") (pinfunction "2_2") (pintype "passive"))
      (node (ref "C24") (pin "2") (pinfunction "2_2") (pintype "passive"))
      (node (ref "C25") (pin "2") (pinfunction "2_2") (pintype "passive"))
      (node (ref "C26") (pin "2") (pinfunction "2_2") (pintype "passive"))
      (node (ref "C27") (pin "2") (pinfunction "2_2") (pintype "passive"))
      (node (ref "C28") (pin "2") (pinfunction "2_2") (pintype "passive"))
      (node (ref "C29") (pin "2") (pinfunction "2_2") (pintype "passive"))
      (node (ref "C3") (pin "1") (pinfunction "1_1") (pintype "passive"))
      (node (ref "C30") (pin "2") (pinfunction "2_2") (pintype "passive"))
      (node (ref "C31") (pin "2") (pinfunction "2_2") (pintype "passive"))
      (node (ref "C4") (pin "2") (pinfunction "2_2") (pintype "passive"))
      (node (ref "C5") (pin "1") (pinfunction "1_1") (pintype "passive"))
      (node (ref "C6") (pin "2") (pinfunction "2_2") (pintype "passive"))
      (node (ref "C7") (pin "2") (pinfunction "2_2") (pintype "passive"))
      (node (ref "C8") (pin "2") (pinfunction "2_2") (pintype "passive"))
      (node (ref "JP11") (pin "1") (pinfunction "1_1") (pintype "passive"))
      (node (ref "JP12") (pin "1") (pinfunction "1_1") (pintype "passive"))
      (node (ref "JP13") (pin "1") (pinfunction "1_1") (pintype "passive"))
      (node (ref "JP2") (pin "1") (pinfunction "1_1") (pintype "passive"))
      (node (ref "JP4") (pin "1") (pinfunction "1_1") (pintype "passive"))
      (node (ref "JP7") (pin "1") (pinfunction "1_1") (pintype "passive"))
      (node (ref "JP8") (pin "1") (pinfunction "1_1") (pintype "passive"))
      (node (ref "JP9") (pin "1") (pinfunction "1_1") (pintype "passive"))
      (node (ref "LED10") (pin "2") (pinfunction "2_2") (pintype "passive"))
      (node (ref "Q1") (pin "2") (pinfunction "2_2") (pintype "passive"))
      (node (ref "Q2") (pin "2") (pinfunction "2_2") (pintype "passive"))
      (node (ref "Q3") (pin "2") (pinfunction "2_2") (pintype "passive"))
      (node (ref "Q4") (pin "2") (pinfunction "2_2") (pintype "passive"))
      (node (ref "Q6") (pin "2") (pinfunction "2_2") (pintype "passive"))
      (node (ref "Q7") (pin "2") (pinfunction "2_2") (pintype "passive"))
      (node (ref "R15") (pin "2") (pinfunction "2_2") (pintype "passive"))
      (node (ref "R18") (pin "2") (pinfunction "2_2") (pintype "passive"))
      (node (ref "R21") (pin "2") (pinfunction "2_2") (pintype "passive"))
      (node (ref "R24") (pin "2") (pinfunction "2_2") (pintype "passive"))
      (node (ref "R27") (pin "2") (pinfunction "2_2") (pintype "passive"))
      (node (ref "R7") (pin "1") (pinfunction "1_1") (pintype "passive"))
      (node (ref "R8") (pin "2") (pinfunction "2_2") (pintype "passive"))
      (node (ref "TP3") (pin "TP") (pinfunction "TP_TP") (pintype "passive"))
      (node (ref "U1") (pin "1") (pinfunction "VBAT_1") (pintype "power_in"))
      (node (ref "U1") (pin "13") (pinfunction "VDDA_13") (pintype "power_in"))
      (node (ref "U1") (pin "19") (pinfunction "VDD_2_19") (pintype "power_in"))
      (node (ref "U1") (pin "32") (pinfunction "VDD_3_32") (pintype "power_in"))
      (node (ref "U1") (pin "48") (pinfunction "VDD_4_48") (pintype "power_in"))
      (node (ref "U2") (pin "2") (pinfunction "OUTPUT_2") (pintype "output"))
      (node (ref "U2") (pin "4") (pinfunction "VOUT_4") (pintype "output"))
      (node (ref "U3") (pin "1") (pinfunction "ENABLE_1_1") (pintype "input"))
      (node (ref "U3") (pin "11") (pinfunction "ENABLE_2_11") (pintype "input"))
    )
    (net (code "3") (name "3VO") (class "Default")
      (node (ref "JP11") (pin "2") (pinfunction "2_2") (pintype "passive"))
    )
    (net (code "4") (name "ADC12_IN4") (class "Default")
      (node (ref "Q1") (pin "1") (pinfunction "1_1") (pintype "passive"))
      (node (ref "R6") (pin "2") (pinfunction "2_2") (pintype "passive"))
      (node (ref "U1") (pin "20") (pinfunction "PA4_20") (pintype "bidirectional"))
    )
    (net (code "5") (name "ADC12_IN5") (class "Default")
      (node (ref "Q2") (pin "1") (pinfunction "1_1") (pintype "passive"))
      (node (ref "R5") (pin "2") (pinfunction "2_2") (pintype "passive"))
      (node (ref "U1") (pin "21") (pinfunction "PA5_21") (pintype "bidirectional"))
    )
    (net (code "6") (name "ADC12_IN6") (class "Default")
      (node (ref "Q3") (pin "1") (pinfunction "1_1") (pintype "passive"))
      (node (ref "R11") (pin "2") (pinfunction "2_2") (pintype "passive"))
      (node (ref "U1") (pin "22") (pinfunction "PA6_22") (pintype "bidirectional"))
    )
    (net (code "7") (name "ADC12_IN7") (class "Default")
      (node (ref "Q4") (pin "1") (pinfunction "1_1") (pintype "passive"))
      (node (ref "R12") (pin "2") (pinfunction "2_2") (pintype "passive"))
      (node (ref "U1") (pin "23") (pinfunction "PA7_23") (pintype "bidirectional"))
    )
    (net (code "8") (name "ADC12_IN8") (class "Default")
      (node (ref "Q6") (pin "1") (pinfunction "1_1") (pintype "passive"))
      (node (ref "R13") (pin "2") (pinfunction "2_2") (pintype "passive"))
      (node (ref "U1") (pin "26") (pinfunction "PB0_26") (pintype "bidirectional"))
    )
    (net (code "9") (name "ADC12_IN9") (class "Default")
      (node (ref "Q7") (pin "1") (pinfunction "1_1") (pintype "passive"))
      (node (ref "R14") (pin "2") (pinfunction "2_2") (pintype "passive"))
      (node (ref "U1") (pin "27") (pinfunction "PB1_27") (pintype "bidirectional"))
    )
    (net (code "10") (name "AGND") (class "Default")
      (node (ref "R11") (pin "1") (pinfunction "1_1") (pintype "passive"))
      (node (ref "R12") (pin "1") (pinfunction "1_1") (pintype "passive"))
      (node (ref "R13") (pin "1") (pinfunction "1_1") (pintype "passive"))
      (node (ref "R14") (pin "1") (pinfunction "1_1") (pintype "passive"))
      (node (ref "R5") (pin "1") (pinfunction "1_1") (pintype "passive"))
      (node (ref "R6") (pin "1") (pinfunction "1_1") (pintype "passive"))
    )
    (net (code "11") (name "DGND") (class "Default")
      (node (ref "C18") (pin "1") (pinfunction "1_1") (pintype "passive"))
      (node (ref "C19") (pin "1") (pinfunction "1_1") (pintype "passive"))
      (node (ref "C20") (pin "1") (pinfunction "1_1") (pintype "passive"))
      (node (ref "C21") (pin "1") (pinfunction "1_1") (pintype "passive"))
      (node (ref "C22") (pin "1") (pinfunction "1_1") (pintype "passive"))
      (node (ref "C23") (pin "1") (pinfunction "1_1") (pintype "passive"))
      (node (ref "C24") (pin "1") (pinfunction "1_1") (pintype "passive"))
      (node (ref "C25") (pin "1") (pinfunction "1_1") (pintype "passive"))
      (node (ref "C26") (pin "1") (pinfunction "1_1") (pintype "passive"))
      (node (ref "C27") (pin "1") (pinfunction "1_1") (pintype "passive"))
      (node (ref "C28") (pin "1") (pinfunction "1_1") (pintype "passive"))
      (node (ref "C29") (pin "1") (pinfunction "1_1") (pintype "passive"))
      (node (ref "C30") (pin "1") (pinfunction "1_1") (pintype "passive"))
      (node (ref "C31") (pin "1") (pinfunction "1_1") (pintype "passive"))
      (node (ref "JP5") (pin "1") (pinfunction "1_1") (pintype "passive"))
      (node (ref "JP6") (pin "1") (pinfunction "1_1") (pintype "passive"))
      (node (ref "Q10") (pin "2") (pinfunction "S_2") (pintype "bidirectional"))
      (node (ref "Q11") (pin "2") (pinfunction "S_2") (pintype "bidirectional"))
      (node (ref "Q12") (pin "2") (pinfunction "S_2") (pintype "bidirectional"))
      (node (ref "Q5") (pin "2") (pinfunction "S_2") (pintype "bidirectional"))
      (node (ref "Q8") (pin "2") (pinfunction "S_2") (pintype "bidirectional"))
      (node (ref "Q9") (pin "2") (pinfunction "S_2") (pintype "bidirectional"))
      (node (ref "R16") (pin "1") (pinfunction "1_1") (pintype "passive"))
      (node (ref "R19") (pin "1") (pinfunction "1_1") (pintype "passive"))
      (node (ref "R22") (pin "1") (pinfunction "1_1") (pintype "passive"))
      (node (ref "R25") (pin "1") (pinfunction "1_1") (pintype "passive"))
      (node (ref "R28") (pin "1") (pinfunction "1_1") (pintype "passive"))
      (node (ref "R31") (pin "1") (pinfunction "1_1") (pintype "passive"))
      (node (ref "R9") (pin "1") (pinfunction "1_1") (pintype "passive"))
    )
    (net (code "12") (name "GND") (class "Default")
      (node (ref "C1") (pin "2") (pinfunction "2_2") (pintype "passive"))
      (node (ref "C10") (pin "1") (pinfunction "1_1") (pintype "passive"))
      (node (ref "C11") (pin "1") (pinfunction "1_1") (pintype "passive"))
      (node (ref "C12") (pin "2") (pinfunction "2_2") (pintype "passive"))
      (node (ref "C13") (pin "1") (pinfunction "1_1") (pintype "passive"))
      (node (ref "C15") (pin "2") (pinfunction "2_2") (pintype "passive"))
      (node (ref "C17") (pin "2") (pinfunction "2_2") (pintype "passive"))
      (node (ref "C2") (pin "2") (pinfunction "2_2") (pintype "passive"))
      (node (ref "C3") (pin "2") (pinfunction "2_2") (pintype "passive"))
      (node (ref "C4") (pin "1") (pinfunction "1_1") (pintype "passive"))
      (node (ref "C5") (pin "2") (pinfunction "2_2") (pintype "passive"))
      (node (ref "C6") (pin "1") (pinfunction "1_1") (pintype "passive"))
      (node (ref "C7") (pin "1") (pinfunction "1_1") (pintype "passive"))
      (node (ref "C8") (pin "1") (pinfunction "1_1") (pintype "passive"))
      (node (ref "C9") (pin "1") (pinfunction "1_1") (pintype "passive"))
      (node (ref "J3") (pin "2") (pinfunction "2_2") (pintype "bidirectional"))
      (node (ref "JP1") (pin "2") (pinfunction "2_2") (pintype "passive"))
      (node (ref "JP11") (pin "3") (pinfunction "3_3") (pintype "passive"))
      (node (ref "JP12") (pin "3") (pinfunction "3_3") (pintype "passive"))
      (node (ref "JP13") (pin "3") (pinfunction "3_3") (pintype "passive"))
      (node (ref "JP2") (pin "4") (pinfunction "4_4") (pintype "passive"))
      (node (ref "JP3") (pin "2") (pinfunction "2_2") (pintype "passive"))
      (node (ref "JP4") (pin "4") (pinfunction "4_4") (pintype "passive"))
      (node (ref "JP7") (pin "3") (pinfunction "3_3") (pintype "passive"))
      (node (ref "JP8") (pin "3") (pinfunction "3_3") (pintype "passive"))
      (node (ref "LED3") (pin "1") (pinfunction "1_1") (pintype "passive"))
      (node (ref "R1") (pin "2") (pinfunction "2_2") (pintype "passive"))
      (node (ref "R2") (pin "1") (pinfunction "1_1") (pintype "passive"))
      (node (ref "R3") (pin "1") (pinfunction "1_1") (pintype "passive"))
      (node (ref "R4") (pin "1") (pinfunction "1_1") (pintype "passive"))
      (node (ref "RESET") (pin "4") (pinfunction "4_4") (pintype "passive"))
      (node (ref "TP2") (pin "TP") (pinfunction "TP_TP") (pintype "passive"))
      (node (ref "U1") (pin "12") (pinfunction "VSSA_12") (pintype "power_in"))
      (node (ref "U1") (pin "18") (pinfunction "VSS_2_18") (pintype "power_in"))
      (node (ref "U1") (pin "63") (pinfunction "VSS_63") (pintype "power_in"))
      (node (ref "U2") (pin "1") (pinfunction "GND_1") (pintype "power_in"))
    )
    (net (code "13") (name "MGND") (class "Default")
      (node (ref "C14") (pin "1") (pinfunction "1_1") (pintype "passive"))
      (node (ref "C16") (pin "1") (pinfunction "1_1") (pintype "passive"))
      (node (ref "Q13") (pin "2") (pinfunction "S_2") (pintype "bidirectional"))
      (node (ref "U3") (pin "14") (pinfunction "GND_14") (pintype "power_in"))
      (node (ref "U3") (pin "15") (pinfunction "GND_15") (pintype "power_in"))
      (node (ref "U3") (pin "16") (pinfunction "GND_16") (pintype "power_in"))
      (node (ref "U3") (pin "17") (pinfunction "GND_17") (pintype "power_in"))
      (node (ref "U3") (pin "4") (pinfunction "GND_4") (pintype "power_in"))
      (node (ref "U3") (pin "5") (pinfunction "GND_5") (pintype "power_in"))
      (node (ref "U3") (pin "6") (pinfunction "GND_6") (pintype "power_in"))
      (node (ref "U3") (pin "7") (pinfunction "GND_7") (pintype "power_in"))
    )
    (net (code "14") (name "ML1") (class "Default")
      (node (ref "MOTOR-BOARD-HEADER-1") (pin "6") (pinfunction "6_6") (pintype "passive"))
      (node (ref "U3") (pin "8") (pinfunction "OUTPUT_2_8") (pintype "output"))
    )
    (net (code "15") (name "ML2") (class "Default")
      (node (ref "MOTOR-BOARD-HEADER-1") (pin "1") (pinfunction "1_1") (pintype "passive"))
      (node (ref "U3") (pin "3") (pinfunction "OUTPUT_1_3") (pintype "output"))
    )
    (net (code "16") (name "MR1") (class "Default")
      (node (ref "MOTOR-BOARD-HEADER-2") (pin "6") (pinfunction "6_6") (pintype "passive"))
      (node (ref "U3") (pin "18") (pinfunction "OUTPUT_4_18") (pintype "output"))
    )
    (net (code "17") (name "MR2") (class "Default")
      (node (ref "MOTOR-BOARD-HEADER-2") (pin "1") (pinfunction "1_1") (pintype "passive"))
      (node (ref "U3") (pin "13") (pinfunction "OUTPUT_3_13") (pintype "output"))
    )
    (net (code "18") (name "N$2") (class "Default")
      (node (ref "C2") (pin "1") (pinfunction "1_1") (pintype "passive"))
      (node (ref "C9") (pin "2") (pinfunction "2_2") (pintype "passive"))
      (node (ref "U1") (pin "47") (pinfunction "VCAP_2_47") (pintype "power_in"))
      (node (ref "U1") (pin "64") (pinfunction "VDD_64") (pintype "power_in"))
    )
    (net (code "19") (name "N$12") (class "Default")
      (node (ref "TP6") (pin "TP") (pinfunction "TP_TP") (pintype "passive"))
    )
    (net (code "20") (name "N$13") (class "Default")
      (node (ref "TP8") (pin "TP") (pinfunction "TP_TP") (pintype "passive"))
    )
    (net (code "21") (name "N$14") (class "Default")
      (node (ref "TP10") (pin "TP") (pinfunction "TP_TP") (pintype "passive"))
    )
    (net (code "22") (name "N$19") (class "Default")
      (node (ref "TP9") (pin "TP") (pinfunction "TP_TP") (pintype "passive"))
    )
    (net (code "23") (name "N$20") (class "Default")
      (node (ref "TP7") (pin "TP") (pinfunction "TP_TP") (pintype "passive"))
    )
    (net (code "24") (name "N$46") (class "Default")
      (node (ref "JP12") (pin "5") (pinfunction "5_5") (pintype "passive"))
      (node (ref "JP13") (pin "5") (pinfunction "5_5") (pintype "passive"))
      (node (ref "JP7") (pin "5") (pinfunction "5_5") (pintype "passive"))
      (node (ref "JP8") (pin "5") (pinfunction "5_5") (pintype "passive"))
    )
    (net (code "25") (name "NRST") (class "Default")
      (node (ref "C11") (pin "2") (pinfunction "2_2") (pintype "passive"))
      (node (ref "JP1") (pin "4") (pinfunction "4_4") (pintype "passive"))
      (node (ref "JP3") (pin "4") (pinfunction "4_4") (pintype "passive"))
      (node (ref "RESET") (pin "1") (pinfunction "1_1") (pintype "passive"))
      (node (ref "TP4") (pin "TP") (pinfunction "TP_TP") (pintype "passive"))
      (node (ref "U1") (pin "7") (pinfunction "NRST_7") (pintype "bidirectional"))
    )
    (net (code "26") (name "Net-(J2-Pad1)") (class "Default")
      (node (ref "J2") (pin "1") (pinfunction "1_1") (pintype "bidirectional"))
      (node (ref "SW1") (pin "1") (pinfunction "1_1") (pintype "passive"))
    )
    (net (code "27") (name "Net-(J2-Pad2)") (class "Default")
      (node (ref "J2") (pin "2") (pinfunction "2_2") (pintype "bidirectional"))
      (node (ref "J3") (pin "1") (pinfunction "1_1") (pintype "bidirectional"))
    )
    (net (code "28") (name "Net-(LED1-Pad1)") (class "Default")
      (node (ref "LED1") (pin "1") (pinfunction "1_1") (pintype "passive"))
      (node (ref "R3") (pin "2") (pinfunction "2_2") (pintype "passive"))
    )
    (net (code "29") (name "Net-(LED2-Pad1)") (class "Default")
      (node (ref "LED2") (pin "1") (pinfunction "1_1") (pintype "passive"))
      (node (ref "R4") (pin "2") (pinfunction "2_2") (pintype "passive"))
    )
    (net (code "30") (name "Net-(LED2-Pad2)") (class "Default")
      (node (ref "LED2") (pin "2") (pinfunction "2_2") (pintype "passive"))
      (node (ref "SW1") (pin "3") (pinfunction "3_3") (pintype "passive"))
    )
    (net (code "31") (name "Net-(LED3-Pad2)") (class "Default")
      (node (ref "LED3") (pin "2") (pinfunction "2_2") (pintype "passive"))
      (node (ref "R7") (pin "2") (pinfunction "2_2") (pintype "passive"))
    )
    (net (code "32") (name "Net-(LED4-Pad2)") (class "Default")
      (node (ref "LED4") (pin "2") (pinfunction "2_2") (pintype "passive"))
      (node (ref "R8") (pin "1") (pinfunction "1_1") (pintype "passive"))
    )
    (net (code "33") (name "Net-(LED5-Pad2)") (class "Default")
      (node (ref "LED5") (pin "2") (pinfunction "2_2") (pintype "passive"))
      (node (ref "R15") (pin "1") (pinfunction "1_1") (pintype "passive"))
    )
    (net (code "34") (name "Net-(LED6-Pad2)") (class "Default")
      (node (ref "LED6") (pin "2") (pinfunction "2_2") (pintype "passive"))
      (node (ref "R18") (pin "1") (pinfunction "1_1") (pintype "passive"))
    )
    (net (code "35") (name "Net-(LED7-Pad2)") (class "Default")
      (node (ref "LED7") (pin "2") (pinfunction "2_2") (pintype "passive"))
      (node (ref "R21") (pin "1") (pinfunction "1_1") (pintype "passive"))
    )
    (net (code "36") (name "Net-(LED8-Pad2)") (class "Default")
      (node (ref "LED8") (pin "2") (pinfunction "2_2") (pintype "passive"))
      (node (ref "R24") (pin "1") (pinfunction "1_1") (pintype "passive"))
    )
    (net (code "37") (name "Net-(LED9-Pad2)") (class "Default")
      (node (ref "LED9") (pin "2") (pinfunction "2_2") (pintype "passive"))
      (node (ref "R27") (pin "1") (pinfunction "1_1") (pintype "passive"))
    )
    (net (code "38") (name "Net-(LED10-Pad1)") (class "Default")
      (node (ref "LED10") (pin "1") (pinfunction "1_1") (pintype "passive"))
      (node (ref "R30") (pin "2") (pinfunction "2_2") (pintype "passive"))
    )
    (net (code "39") (name "Net-(Q5-D)") (class "Default")
      (node (ref "LED4") (pin "1") (pinfunction "1_1") (pintype "passive"))
      (node (ref "Q5") (pin "3") (pinfunction "D_3") (pintype "bidirectional"))
    )
    (net (code "40") (name "Net-(Q5-G)") (class "Default")
      (node (ref "Q5") (pin "1") (pinfunction "G_1") (pintype "bidirectional"))
      (node (ref "R10") (pin "1") (pinfunction "1_1") (pintype "passive"))
      (node (ref "R9") (pin "2") (pinfunction "2_2") (pintype "passive"))
    )
    (net (code "41") (name "Net-(Q8-D)") (class "Default")
      (node (ref "LED5") (pin "1") (pinfunction "1_1") (pintype "passive"))
      (node (ref "Q8") (pin "3") (pinfunction "D_3") (pintype "bidirectional"))
    )
    (net (code "42") (name "Net-(Q8-G)") (class "Default")
      (node (ref "Q8") (pin "1") (pinfunction "G_1") (pintype "bidirectional"))
      (node (ref "R16") (pin "2") (pinfunction "2_2") (pintype "passive"))
      (node (ref "R17") (pin "1") (pinfunction "1_1") (pintype "passive"))
    )
    (net (code "43") (name "Net-(Q9-D)") (class "Default")
      (node (ref "LED6") (pin "1") (pinfunction "1_1") (pintype "passive"))
      (node (ref "Q9") (pin "3") (pinfunction "D_3") (pintype "bidirectional"))
    )
    (net (code "44") (name "Net-(Q9-G)") (class "Default")
      (node (ref "Q9") (pin "1") (pinfunction "G_1") (pintype "bidirectional"))
      (node (ref "R19") (pin "2") (pinfunction "2_2") (pintype "passive"))
      (node (ref "R20") (pin "1") (pinfunction "1_1") (pintype "passive"))
    )
    (net (code "45") (name "Net-(Q10-D)") (class "Default")
      (node (ref "LED7") (pin "1") (pinfunction "1_1") (pintype "passive"))
      (node (ref "Q10") (pin "3") (pinfunction "D_3") (pintype "bidirectional"))
    )
    (net (code "46") (name "Net-(Q10-G)") (class "Default")
      (node (ref "Q10") (pin "1") (pinfunction "G_1") (pintype "bidirectional"))
      (node (ref "R22") (pin "2") (pinfunction "2_2") (pintype "passive"))
      (node (ref "R23") (pin "1") (pinfunction "1_1") (pintype "passive"))
    )
    (net (code "47") (name "Net-(Q11-D)") (class "Default")
      (node (ref "LED8") (pin "1") (pinfunction "1_1") (pintype "passive"))
      (node (ref "Q11") (pin "3") (pinfunction "D_3") (pintype "bidirectional"))
    )
    (net (code "48") (name "Net-(Q11-G)") (class "Default")
      (node (ref "Q11") (pin "1") (pinfunction "G_1") (pintype "bidirectional"))
      (node (ref "R25") (pin "2") (pinfunction "2_2") (pintype "passive"))
      (node (ref "R26") (pin "1") (pinfunction "1_1") (pintype "passive"))
    )
    (net (code "49") (name "Net-(Q12-D)") (class "Default")
      (node (ref "LED9") (pin "1") (pinfunction "1_1") (pintype "passive"))
      (node (ref "Q12") (pin "3") (pinfunction "D_3") (pintype "bidirectional"))
    )
    (net (code "50") (name "Net-(Q12-G)") (class "Default")
      (node (ref "Q12") (pin "1") (pinfunction "G_1") (pintype "bidirectional"))
      (node (ref "R28") (pin "2") (pinfunction "2_2") (pintype "passive"))
      (node (ref "R29") (pin "1") (pinfunction "1_1") (pintype "passive"))
    )
    (net (code "51") (name "Net-(Q13-D)") (class "Default")
      (node (ref "JP9") (pin "2") (pinfunction "2_2") (pintype "passive"))
      (node (ref "Q13") (pin "3") (pinfunction "D_3") (pintype "bidirectional"))
      (node (ref "R30") (pin "1") (pinfunction "1_1") (pintype "passive"))
    )
    (net (code "52") (name "Net-(Q13-G)") (class "Default")
      (node (ref "Q13") (pin "1") (pinfunction "G_1") (pintype "bidirectional"))
      (node (ref "R31") (pin "2") (pinfunction "2_2") (pintype "passive"))
      (node (ref "R32") (pin "1") (pinfunction "1_1") (pintype "passive"))
    )
    (net (code "53") (name "Net-(U1A-BOOT0)") (class "Default")
      (node (ref "R1") (pin "1") (pinfunction "1_1") (pintype "passive"))
      (node (ref "U1") (pin "60") (pinfunction "BOOT0_60") (pintype "input"))
    )
    (net (code "54") (name "Net-(U1A-PB2)") (class "Default")
      (node (ref "R2") (pin "2") (pinfunction "2_2") (pintype "passive"))
      (node (ref "U1") (pin "28") (pinfunction "PB2_28") (pintype "bidirectional"))
    )
    (net (code "55") (name "Net-(U1B-VCAP_1)") (class "Default")
      (node (ref "C1") (pin "1") (pinfunction "1_1") (pintype "passive"))
      (node (ref "U1") (pin "31") (pinfunction "VCAP_1_31") (pintype "power_in"))
    )
    (net (code "56") (name "PA12") (class "Default")
      (node (ref "R32") (pin "2") (pinfunction "2_2") (pintype "passive"))
      (node (ref "TP5") (pin "TP") (pinfunction "TP_TP") (pintype "passive"))
      (node (ref "U1") (pin "45") (pinfunction "PA12_45") (pintype "bidirectional"))
    )
    (net (code "57") (name "PA15") (class "Default")
      (node (ref "U1") (pin "50") (pinfunction "PA15_50") (pintype "bidirectional"))
    )
    (net (code "58") (name "PB3") (class "Default")
      (node (ref "R17") (pin "2") (pinfunction "2_2") (pintype "passive"))
      (node (ref "U1") (pin "55") (pinfunction "PB3_55") (pintype "bidirectional"))
    )
    (net (code "59") (name "PB4") (class "Default")
      (node (ref "R10") (pin "2") (pinfunction "2_2") (pintype "passive"))
      (node (ref "U1") (pin "56") (pinfunction "PB4_56") (pintype "bidirectional"))
    )
    (net (code "60") (name "PB5") (class "Default")
      (node (ref "R20") (pin "2") (pinfunction "2_2") (pintype "passive"))
      (node (ref "U1") (pin "57") (pinfunction "PB5_57") (pintype "bidirectional"))
    )
    (net (code "61") (name "PB12") (class "Default")
      (node (ref "U1") (pin "33") (pinfunction "PB12_33") (pintype "bidirectional"))
    )
    (net (code "62") (name "PB13") (class "Default")
      (node (ref "R23") (pin "2") (pinfunction "2_2") (pintype "passive"))
      (node (ref "U1") (pin "34") (pinfunction "PB13_34") (pintype "bidirectional"))
    )
    (net (code "63") (name "PB14") (class "Default")
      (node (ref "R26") (pin "2") (pinfunction "2_2") (pintype "passive"))
      (node (ref "U1") (pin "35") (pinfunction "PB14_35") (pintype "bidirectional"))
    )
    (net (code "64") (name "PB15") (class "Default")
      (node (ref "R29") (pin "2") (pinfunction "2_2") (pintype "passive"))
      (node (ref "U1") (pin "36") (pinfunction "PB15_36") (pintype "bidirectional"))
    )
    (net (code "65") (name "PC0") (class "Default")
      (node (ref "U1") (pin "8") (pinfunction "PC0_8") (pintype "bidirectional"))
    )
    (net (code "66") (name "PC1") (class "Default")
      (node (ref "U1") (pin "9") (pinfunction "PC1_9") (pintype "bidirectional"))
    )
    (net (code "67") (name "PC2") (class "Default")
      (node (ref "U1") (pin "10") (pinfunction "PC2_10") (pintype "bidirectional"))
    )
    (net (code "68") (name "PC3") (class "Default")
      (node (ref "U1") (pin "11") (pinfunction "PC3_11") (pintype "bidirectional"))
    )
    (net (code "69") (name "PC4") (class "Default")
      (node (ref "U1") (pin "24") (pinfunction "PC4_24") (pintype "bidirectional"))
    )
    (net (code "70") (name "PC5") (class "Default")
      (node (ref "U1") (pin "25") (pinfunction "PC5_25") (pintype "bidirectional"))
    )
    (net (code "71") (name "PC12") (class "Default")
      (node (ref "U1") (pin "53") (pinfunction "PC12_53") (pintype "bidirectional"))
    )
    (net (code "72") (name "PC13") (class "Default")
      (node (ref "U1") (pin "2") (pinfunction "PC13_2") (pintype "bidirectional"))
    )
    (net (code "73") (name "PC14-OSC32_IN") (class "Default")
      (node (ref "U1") (pin "3") (pinfunction "PC14/OSC32_IN_3") (pintype "bidirectional"))
    )
    (net (code "74") (name "PC15-OSC32_OUT") (class "Default")
      (node (ref "U1") (pin "4") (pinfunction "PC15-OSC32_OUT_4") (pintype "bidirectional"))
    )
    (net (code "75") (name "PD2") (class "Default")
      (node (ref "U1") (pin "54") (pinfunction "PD2_54") (pintype "bidirectional"))
    )
    (net (code "76") (name "PH0-OSC_IN") (class "Default")
      (node (ref "U1") (pin "5") (pinfunction "PH0/OSC_IN_5") (pintype "bidirectional"))
    )
    (net (code "77") (name "PH1-OSC_OUT") (class "Default")
      (node (ref "U1") (pin "6") (pinfunction "PH1/OSC_OUT_6") (pintype "bidirectional"))
    )
    (net (code "78") (name "S3V3") (class "Default")
      (node (ref "MOTOR-BOARD-HEADER-1") (pin "2") (pinfunction "2_2") (pintype "passive"))
      (node (ref "MOTOR-BOARD-HEADER-2") (pin "2") (pinfunction "2_2") (pintype "passive"))
    )
    (net (code "79") (name "SCL") (class "Default")
      (node (ref "JP11") (pin "4") (pinfunction "4_4") (pintype "passive"))
      (node (ref "JP12") (pin "6") (pinfunction "6_6") (pintype "passive"))
      (node (ref "JP13") (pin "6") (pinfunction "6_6") (pintype "passive"))
      (node (ref "JP7") (pin "6") (pinfunction "6_6") (pintype "passive"))
      (node (ref "JP8") (pin "6") (pinfunction "6_6") (pintype "passive"))
      (node (ref "TP13") (pin "TP") (pinfunction "TP_TP") (pintype "passive"))
      (node (ref "U1") (pin "29") (pinfunction "PB10_29") (pintype "bidirectional"))
    )
    (net (code "80") (name "SDA") (class "Default")
      (node (ref "JP11") (pin "5") (pinfunction "5_5") (pintype "passive"))
      (node (ref "JP12") (pin "7") (pinfunction "7_7") (pintype "passive"))
      (node (ref "JP13") (pin "7") (pinfunction "7_7") (pintype "passive"))
      (node (ref "JP7") (pin "7") (pinfunction "7_7") (pintype "passive"))
      (node (ref "JP8") (pin "7") (pinfunction "7_7") (pintype "passive"))
      (node (ref "TP14") (pin "TP") (pinfunction "TP_TP") (pintype "passive"))
      (node (ref "U1") (pin "30") (pinfunction "PB11_30") (pintype "bidirectional"))
    )
    (net (code "81") (name "SGND") (class "Default")
      (node (ref "MOTOR-BOARD-HEADER-1") (pin "5") (pinfunction "5_5") (pintype "passive"))
      (node (ref "MOTOR-BOARD-HEADER-2") (pin "5") (pinfunction "5_5") (pintype "passive"))
    )
    (net (code "82") (name "SHDN") (class "Default")
      (node (ref "JP12") (pin "4") (pinfunction "4_4") (pintype "passive"))
      (node (ref "JP13") (pin "4") (pinfunction "4_4") (pintype "passive"))
      (node (ref "JP7") (pin "4") (pinfunction "4_4") (pintype "passive"))
      (node (ref "JP8") (pin "4") (pinfunction "4_4") (pintype "passive"))
    )
    (net (code "83") (name "SWCLK") (class "Default")
      (node (ref "JP1") (pin "1") (pinfunction "1_1") (pintype "passive"))
      (node (ref "JP3") (pin "1") (pinfunction "1_1") (pintype "passive"))
      (node (ref "U1") (pin "49") (pinfunction "PA14_49") (pintype "bidirectional"))
    )
    (net (code "84") (name "SWDIO") (class "Default")
      (node (ref "JP1") (pin "3") (pinfunction "3_3") (pintype "passive"))
      (node (ref "JP3") (pin "3") (pinfunction "3_3") (pintype "passive"))
      (node (ref "U1") (pin "46") (pinfunction "PA13_46") (pintype "bidirectional"))
    )
    (net (code "85") (name "TIM1_CH1") (class "Default")
      (node (ref "MOTOR-BOARD-HEADER-2") (pin "3") (pinfunction "3_3") (pintype "passive"))
      (node (ref "U1") (pin "41") (pinfunction "PA8_41") (pintype "bidirectional"))
    )
    (net (code "86") (name "TIM1_CH2") (class "Default")
      (node (ref "MOTOR-BOARD-HEADER-2") (pin "4") (pinfunction "4_4") (pintype "passive"))
      (node (ref "U1") (pin "42") (pinfunction "PA9_42") (pintype "bidirectional"))
    )
    (net (code "87") (name "TIM1_CH3") (class "Default")
      (node (ref "U1") (pin "43") (pinfunction "PA10_43") (pintype "bidirectional"))
    )
    (net (code "88") (name "TIM1_CH4") (class "Default")
      (node (ref "U1") (pin "44") (pinfunction "PA11_44") (pintype "bidirectional"))
    )
    (net (code "89") (name "TIM2_CH1_ETR") (class "Default")
      (node (ref "MOTOR-BOARD-HEADER-1") (pin "3") (pinfunction "3_3") (pintype "passive"))
      (node (ref "U1") (pin "14") (pinfunction "PA0-WKUP_14") (pintype "bidirectional"))
    )
    (net (code "90") (name "TIM2_CH2") (class "Default")
      (node (ref "MOTOR-BOARD-HEADER-1") (pin "4") (pinfunction "4_4") (pintype "passive"))
      (node (ref "U1") (pin "15") (pinfunction "PA1_15") (pintype "bidirectional"))
    )
    (net (code "91") (name "TIM2_CH3") (class "Default")
      (node (ref "U1") (pin "16") (pinfunction "PA2_16") (pintype "bidirectional"))
    )
    (net (code "92") (name "TIM2_CH4") (class "Default")
      (node (ref "U1") (pin "17") (pinfunction "PA3_17") (pintype "bidirectional"))
    )
    (net (code "93") (name "TIM3_CH1") (class "Default")
      (node (ref "JP5") (pin "2") (pinfunction "2_2") (pintype "passive"))
      (node (ref "U1") (pin "37") (pinfunction "PC6_37") (pintype "bidirectional"))
    )
    (net (code "94") (name "TIM3_CH2") (class "Default")
      (node (ref "JP6") (pin "2") (pinfunction "2_2") (pintype "passive"))
      (node (ref "U1") (pin "38") (pinfunction "PC7_38") (pintype "bidirectional"))
    )
    (net (code "95") (name "TIM3_CH3") (class "Default")
      (node (ref "U1") (pin "39") (pinfunction "PC8_39") (pintype "bidirectional"))
    )
    (net (code "96") (name "TIM3_CH4") (class "Default")
      (node (ref "U1") (pin "40") (pinfunction "PC9_40") (pintype "bidirectional"))
    )
    (net (code "97") (name "TIM4_CH1") (class "Default")
      (node (ref "U1") (pin "58") (pinfunction "PB6_58") (pintype "bidirectional"))
      (node (ref "U3") (pin "2") (pinfunction "INPUT_1_2") (pintype "input"))
    )
    (net (code "98") (name "TIM4_CH2") (class "Default")
      (node (ref "U1") (pin "59") (pinfunction "PB7_59") (pintype "bidirectional"))
      (node (ref "U3") (pin "9") (pinfunction "INPUT_2_9") (pintype "input"))
    )
    (net (code "99") (name "TIM4_CH3") (class "Default")
      (node (ref "U1") (pin "61") (pinfunction "PB8_61") (pintype "bidirectional"))
      (node (ref "U3") (pin "12") (pinfunction "INPUT_3_12") (pintype "input"))
    )
    (net (code "100") (name "TIM4_CH4") (class "Default")
      (node (ref "U1") (pin "62") (pinfunction "PB9_62") (pintype "bidirectional"))
      (node (ref "U3") (pin "19") (pinfunction "INPUT_4_19") (pintype "input"))
    )
    (net (code "101") (name "USART3_RX") (class "Default")
      (node (ref "JP2") (pin "3") (pinfunction "3_3") (pintype "passive"))
      (node (ref "JP4") (pin "3") (pinfunction "3_3") (pintype "passive"))
      (node (ref "TP11") (pin "TP") (pinfunction "TP_TP") (pintype "passive"))
      (node (ref "U1") (pin "52") (pinfunction "PC11_52") (pintype "bidirectional"))
    )
    (net (code "102") (name "USART3_TX") (class "Default")
      (node (ref "JP2") (pin "2") (pinfunction "2_2") (pintype "passive"))
      (node (ref "JP4") (pin "2") (pinfunction "2_2") (pintype "passive"))
      (node (ref "TP12") (pin "TP") (pinfunction "TP_TP") (pintype "passive"))
      (node (ref "U1") (pin "51") (pinfunction "PC10_51") (pintype "bidirectional"))
    )
    (net (code "103") (name "VCC") (class "Default")
      (node (ref "C12") (pin "1") (pinfunction "1_1") (pintype "passive"))
      (node (ref "C14") (pin "2") (pinfunction "2_2") (pintype "passive"))
      (node (ref "C15") (pin "1") (pinfunction "1_1") (pintype "passive"))
      (node (ref "C16") (pin "2") (pinfunction "2_2") (pintype "passive"))
      (node (ref "C17") (pin "1") (pinfunction "1_1") (pintype "passive"))
      (node (ref "LED1") (pin "2") (pinfunction "2_2") (pintype "passive"))
      (node (ref "SW1") (pin "2") (pinfunction "2_2") (pintype "passive"))
      (node (ref "TP1") (pin "TP") (pinfunction "TP_TP") (pintype "passive"))
      (node (ref "U2") (pin "3") (pinfunction "INPUT_3") (pintype "input"))
      (node (ref "U3") (pin "10") (pinfunction "VS_10") (pintype "power_in"))
      (node (ref "U3") (pin "20") (pinfunction "VSS_20") (pintype "power_in"))
    )
    (net (code "104") (name "unconnected-(RESET-Pad2)") (class "Default")
      (node (ref "RESET") (pin "2") (pinfunction "2_2") (pintype "passive"))
    )
    (net (code "105") (name "unconnected-(RESET-Pad3)") (class "Default")
      (node (ref "RESET") (pin "3") (pinfunction "3_3") (pintype "passive"))
    )
  )
)
